# esc_control.net
KiCad netlist of a schematic drawn in EAGLE
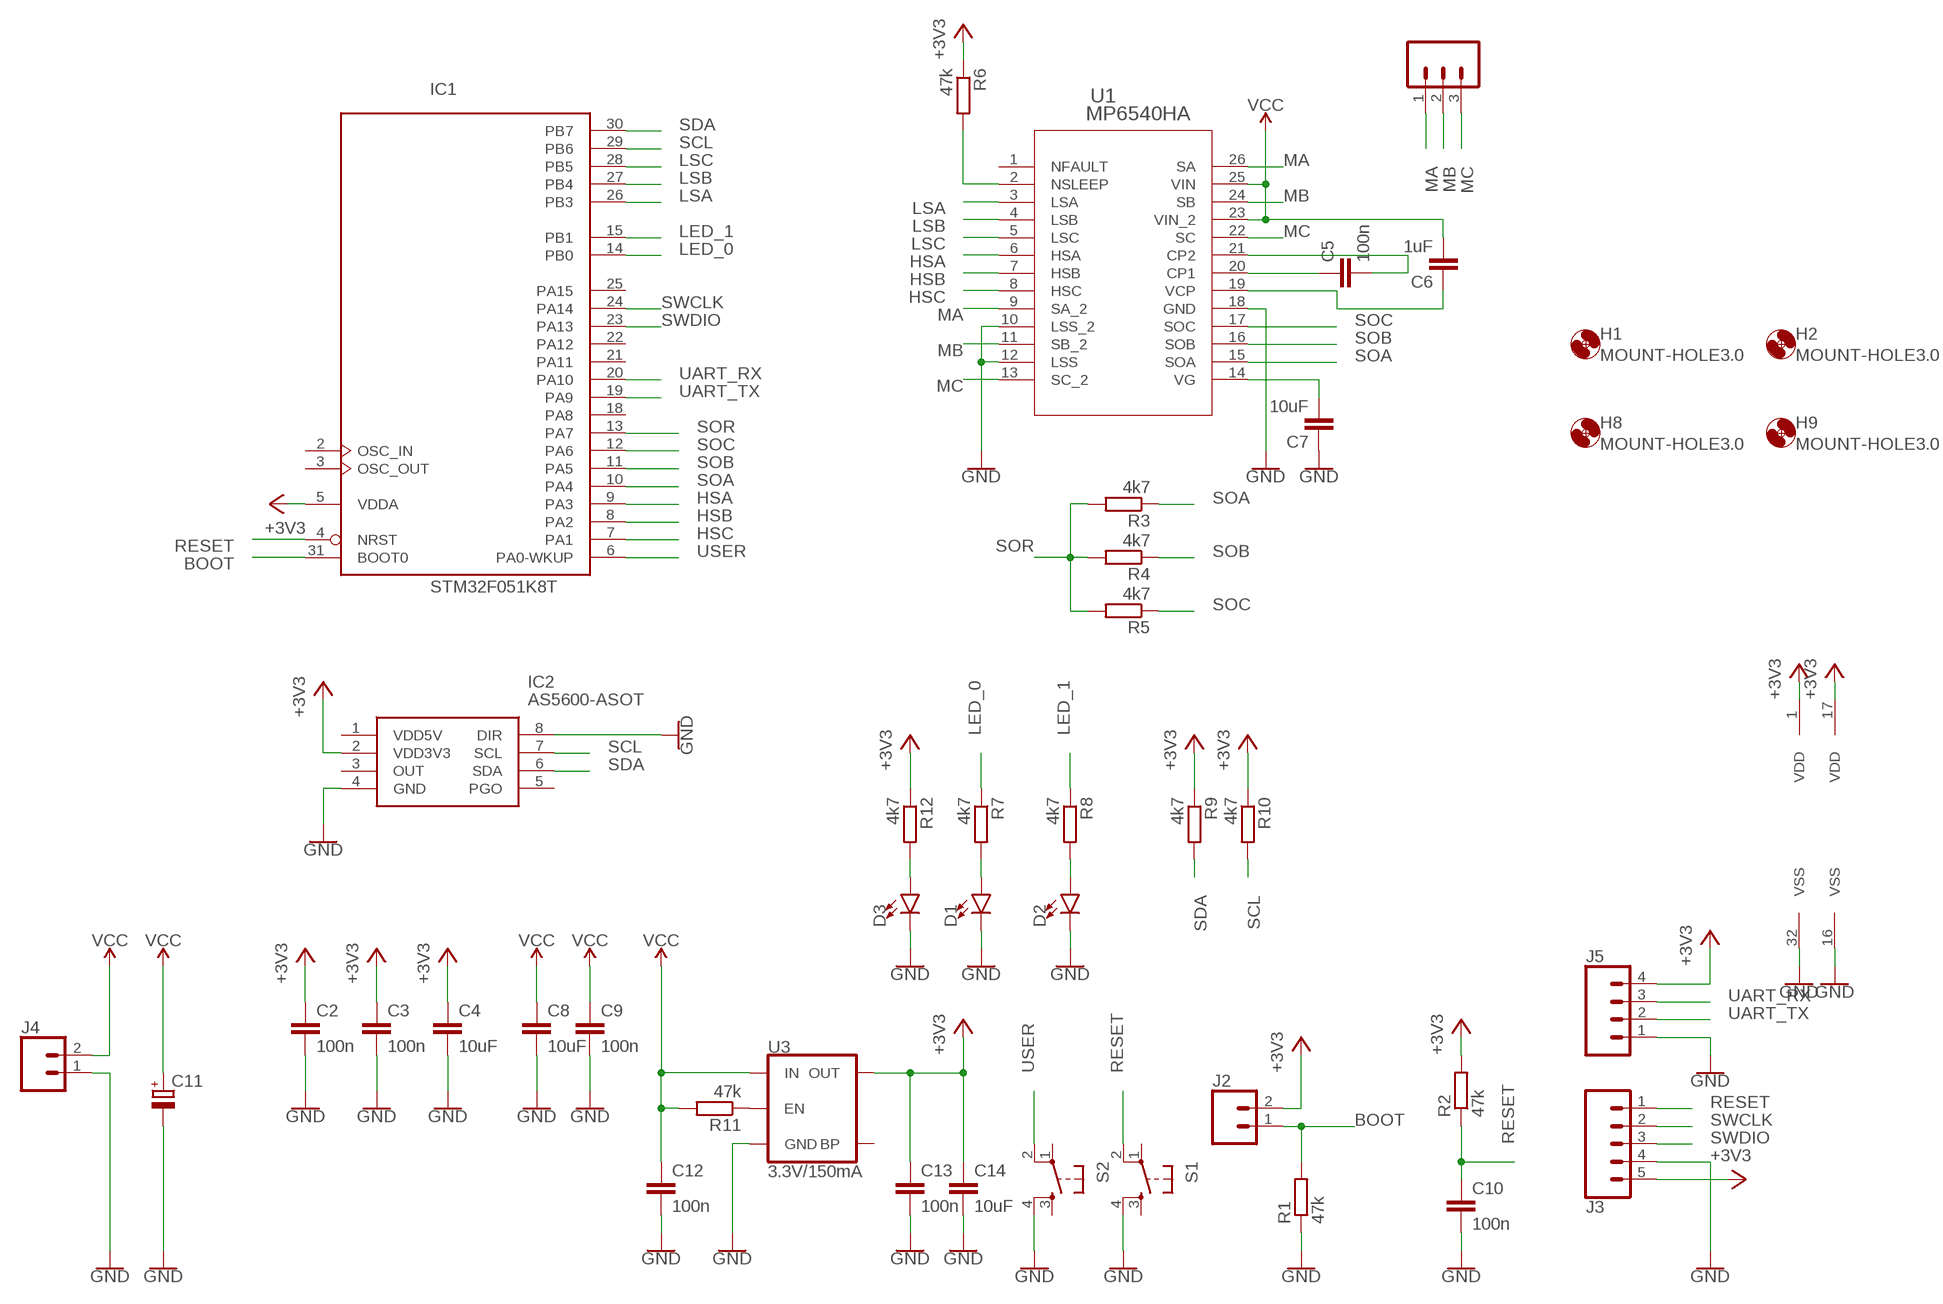
[diagram p0: schematic, sheet 1]

(export (version "E")
  (design (tool "Eeschema 10.0.6"))
  (components
    (comp (ref "C2")
      (value "100n")
      (footprint "eagle-import:C0805")
      (libsource (lib "eagle-import") (part "C-EUC0805"))
    )
    (comp (ref "C3")
      (value "100n")
      (footprint "eagle-import:C0805")
      (libsource (lib "eagle-import") (part "C-EUC0805"))
    )
    (comp (ref "C4")
      (value "10uF")
      (footprint "eagle-import:C0805")
      (libsource (lib "eagle-import") (part "C-EUC0805"))
    )
    (comp (ref "C5")
      (value "100n")
      (footprint "eagle-import:C0805")
      (libsource (lib "eagle-import") (part "C-EUC0805"))
    )
    (comp (ref "C6")
      (value "1uF")
      (footprint "eagle-import:C0805")
      (libsource (lib "eagle-import") (part "C-EUC0805"))
    )
    (comp (ref "C7")
      (value "10uF")
      (footprint "eagle-import:C0805")
      (libsource (lib "eagle-import") (part "C-EUC0805"))
    )
    (comp (ref "C8")
      (value "10uF")
      (footprint "eagle-import:C0805")
      (libsource (lib "eagle-import") (part "C-EUC0805"))
    )
    (comp (ref "C9")
      (value "100n")
      (footprint "eagle-import:C0805")
      (libsource (lib "eagle-import") (part "C-EUC0805"))
    )
    (comp (ref "C10")
      (value "100n")
      (footprint "eagle-import:C0805")
      (libsource (lib "eagle-import") (part "C-EUC0805"))
    )
    (comp (ref "C11")
      (value "CPOL-EU153CLV-0605")
      (footprint "eagle-import:153CLV-0605")
      (libsource (lib "eagle-import") (part "CPOL-EU153CLV-0605"))
    )
    (comp (ref "C12")
      (value "100n")
      (footprint "eagle-import:C0805")
      (libsource (lib "eagle-import") (part "C-EUC0805"))
    )
    (comp (ref "C13")
      (value "100n")
      (footprint "eagle-import:C0805")
      (libsource (lib "eagle-import") (part "C-EUC0805"))
    )
    (comp (ref "C14")
      (value "10uF")
      (footprint "eagle-import:C0805")
      (libsource (lib "eagle-import") (part "C-EUC0805"))
    )
    (comp (ref "D1")
      (value "LED1206")
      (footprint "eagle-import:LED-1206")
      (libsource (lib "eagle-import") (part "LED1206"))
    )
    (comp (ref "D2")
      (value "LED1206")
      (footprint "eagle-import:LED-1206")
      (libsource (lib "eagle-import") (part "LED1206"))
    )
    (comp (ref "D3")
      (value "LED1206")
      (footprint "eagle-import:LED-1206")
      (libsource (lib "eagle-import") (part "LED1206"))
    )
    (comp (ref "H1")
      (value "MOUNT-HOLE3.0")
      (footprint "eagle-import:3,0")
      (libsource (lib "eagle-import") (part "MOUNT-HOLE3.0"))
    )
    (comp (ref "H2")
      (value "MOUNT-HOLE3.0")
      (footprint "eagle-import:3,0")
      (libsource (lib "eagle-import") (part "MOUNT-HOLE3.0"))
    )
    (comp (ref "H8")
      (value "MOUNT-HOLE3.0")
      (footprint "eagle-import:3,0")
      (libsource (lib "eagle-import") (part "MOUNT-HOLE3.0"))
    )
    (comp (ref "H9")
      (value "MOUNT-HOLE3.0")
      (footprint "eagle-import:3,0")
      (libsource (lib "eagle-import") (part "MOUNT-HOLE3.0"))
    )
    (comp (ref "IC1")
      (value "STM32F051K8T")
      (footprint "eagle-import:LQFP32")
      (libsource (lib "eagle-import") (part "STM32F051KT8"))
    )
    (comp (ref "IC2")
      (value "AS5600-ASOT")
      (footprint "eagle-import:SOIC127P600X175-8N")
      (fields (field (name "MOUSER_PART_NUMBER") "985-AS5600-ASOT"))
      (libsource (lib "eagle-import") (part "AS5600-ASOT"))
    )
    (comp (ref "J1")
      (value "455-1750-1-ND")
      (footprint "eagle-import:1X03")
      (libsource (lib "eagle-import") (part "CONN_03"))
    )
    (comp (ref "J2")
      (value "CONN_02PTH3")
      (footprint "eagle-import:1X02_LONGPADS")
      (libsource (lib "eagle-import") (part "CONN_02PTH3"))
    )
    (comp (ref "J3")
      (value "CONN_05PTH_LONGPADS")
      (footprint "eagle-import:1X05_LONGPADS")
      (libsource (lib "eagle-import") (part "CONN_05PTH_LONGPADS"))
    )
    (comp (ref "J4")
      (value "CONN_02PTH3")
      (footprint "eagle-import:1X02_LONGPADS")
      (libsource (lib "eagle-import") (part "CONN_02PTH3"))
    )
    (comp (ref "J5")
      (value "CONN_04LONGPADS")
      (footprint "eagle-import:1X04_LONGPADS")
      (libsource (lib "eagle-import") (part "CONN_04LONGPADS"))
    )
    (comp (ref "R1")
      (value "47k")
      (footprint "eagle-import:M0805")
      (libsource (lib "eagle-import") (part "R-EU_M0805"))
    )
    (comp (ref "R2")
      (value "47k")
      (footprint "eagle-import:M0805")
      (libsource (lib "eagle-import") (part "R-EU_M0805"))
    )
    (comp (ref "R3")
      (value "4k7")
      (footprint "eagle-import:M0805")
      (libsource (lib "eagle-import") (part "R-EU_M0805"))
    )
    (comp (ref "R4")
      (value "4k7")
      (footprint "eagle-import:M0805")
      (libsource (lib "eagle-import") (part "R-EU_M0805"))
    )
    (comp (ref "R5")
      (value "4k7")
      (footprint "eagle-import:M0805")
      (libsource (lib "eagle-import") (part "R-EU_M0805"))
    )
    (comp (ref "R6")
      (value "47k")
      (footprint "eagle-import:M0805")
      (libsource (lib "eagle-import") (part "R-EU_M0805"))
    )
    (comp (ref "R7")
      (value "4k7")
      (footprint "eagle-import:M0805")
      (libsource (lib "eagle-import") (part "R-EU_M0805"))
    )
    (comp (ref "R8")
      (value "4k7")
      (footprint "eagle-import:M0805")
      (libsource (lib "eagle-import") (part "R-EU_M0805"))
    )
    (comp (ref "R9")
      (value "4k7")
      (footprint "eagle-import:M0805")
      (libsource (lib "eagle-import") (part "R-EU_M0805"))
    )
    (comp (ref "R10")
      (value "4k7")
      (footprint "eagle-import:M0805")
      (libsource (lib "eagle-import") (part "R-EU_M0805"))
    )
    (comp (ref "R11")
      (value "47k")
      (footprint "eagle-import:M0805")
      (libsource (lib "eagle-import") (part "R-EU_M0805"))
    )
    (comp (ref "R12")
      (value "4k7")
      (footprint "eagle-import:M0805")
      (libsource (lib "eagle-import") (part "R-EU_M0805"))
    )
    (comp (ref "S1")
      (value "TAC_SWITCHSMD")
      (footprint "eagle-import:TACTILE-SWITCH-SMD")
      (libsource (lib "eagle-import") (part "TAC_SWITCHSMD"))
    )
    (comp (ref "S2")
      (value "TAC_SWITCHSMD")
      (footprint "eagle-import:TACTILE-SWITCH-SMD")
      (libsource (lib "eagle-import") (part "TAC_SWITCHSMD"))
    )
    (comp (ref "U1")
      (value "MP6540HA")
      (footprint "eagle-import:QFN-5X5_MP6540HA_MNP")
      (fields (field (name "COPYRIGHT") "Copyright (C) 2018 Accelerated Designs. All rights reserved"))
      (libsource (lib "eagle-import") (part "MP6540HA"))
    )
    (comp (ref "U3")
      (value "3.3V/150mA")
      (footprint "eagle-import:SOT23-5")
      (libsource (lib "eagle-import") (part "V_REG_MIC52053.3V"))
    )
  )
  (nets
    (net (code "1") (name "+3V3") (class "Default")
      (node (ref "C13") (pin "1") (pinfunction "1_1") (pintype "passive"))
      (node (ref "C14") (pin "1") (pinfunction "1_1") (pintype "passive"))
      (node (ref "C2") (pin "1") (pinfunction "1_1") (pintype "passive"))
      (node (ref "C3") (pin "1") (pinfunction "1_1") (pintype "passive"))
      (node (ref "C4") (pin "1") (pinfunction "1_1") (pintype "passive"))
      (node (ref "IC1") (pin "1") (pinfunction "VDD_1") (pintype "power_in"))
      (node (ref "IC1") (pin "17") (pinfunction "VDD_17") (pintype "power_in"))
      (node (ref "IC1") (pin "5") (pinfunction "VDDA_5") (pintype "power_in"))
      (node (ref "IC2") (pin "2") (pinfunction "VDD3V3_2") (pintype "bidirectional"))
      (node (ref "J2") (pin "2") (pinfunction "2_2") (pintype "passive"))
      (node (ref "J3") (pin "5") (pinfunction "5_5") (pintype "passive"))
      (node (ref "J5") (pin "4") (pinfunction "4_4") (pintype "passive"))
      (node (ref "R10") (pin "1") (pinfunction "1_1") (pintype "passive"))
      (node (ref "R12") (pin "1") (pinfunction "1_1") (pintype "passive"))
      (node (ref "R2") (pin "2") (pinfunction "2_2") (pintype "passive"))
      (node (ref "R6") (pin "1") (pinfunction "1_1") (pintype "passive"))
      (node (ref "R9") (pin "1") (pinfunction "1_1") (pintype "passive"))
      (node (ref "U3") (pin "5") (pinfunction "OUT_5") (pintype "passive"))
    )
    (net (code "2") (name "/BOOT") (class "Default")
      (node (ref "IC1") (pin "31") (pinfunction "BOOT0_31") (pintype "input"))
      (node (ref "J2") (pin "1") (pinfunction "1_1") (pintype "passive"))
      (node (ref "R1") (pin "2") (pinfunction "2_2") (pintype "passive"))
    )
    (net (code "3") (name "/HSA") (class "Default")
      (node (ref "IC1") (pin "9") (pinfunction "PA3_9") (pintype "bidirectional"))
      (node (ref "U1") (pin "6") (pinfunction "HSA_6") (pintype "passive"))
    )
    (net (code "4") (name "/HSB") (class "Default")
      (node (ref "IC1") (pin "8") (pinfunction "PA2_8") (pintype "bidirectional"))
      (node (ref "U1") (pin "7") (pinfunction "HSB_7") (pintype "passive"))
    )
    (net (code "5") (name "/HSC") (class "Default")
      (node (ref "IC1") (pin "7") (pinfunction "PA1_7") (pintype "bidirectional"))
      (node (ref "U1") (pin "8") (pinfunction "HSC_8") (pintype "passive"))
    )
    (net (code "6") (name "/LED_0") (class "Default")
      (node (ref "IC1") (pin "14") (pinfunction "PB0_14") (pintype "bidirectional"))
      (node (ref "R7") (pin "1") (pinfunction "1_1") (pintype "passive"))
    )
    (net (code "7") (name "/LED_1") (class "Default")
      (node (ref "IC1") (pin "15") (pinfunction "PB1_15") (pintype "bidirectional"))
      (node (ref "R8") (pin "1") (pinfunction "1_1") (pintype "passive"))
    )
    (net (code "8") (name "/LSA") (class "Default")
      (node (ref "IC1") (pin "26") (pinfunction "PB3_26") (pintype "bidirectional"))
      (node (ref "U1") (pin "3") (pinfunction "LSA_3") (pintype "passive"))
    )
    (net (code "9") (name "/LSB") (class "Default")
      (node (ref "IC1") (pin "27") (pinfunction "PB4_27") (pintype "bidirectional"))
      (node (ref "U1") (pin "4") (pinfunction "LSB_4") (pintype "passive"))
    )
    (net (code "10") (name "/LSC") (class "Default")
      (node (ref "IC1") (pin "28") (pinfunction "PB5_28") (pintype "bidirectional"))
      (node (ref "U1") (pin "5") (pinfunction "LSC_5") (pintype "passive"))
    )
    (net (code "11") (name "/MA") (class "Default")
      (node (ref "J1") (pin "1") (pinfunction "1_1") (pintype "passive"))
      (node (ref "U1") (pin "26") (pinfunction "SA_26") (pintype "output"))
      (node (ref "U1") (pin "9") (pinfunction "SA_2_9") (pintype "output"))
    )
    (net (code "12") (name "/MB") (class "Default")
      (node (ref "J1") (pin "2") (pinfunction "2_2") (pintype "passive"))
      (node (ref "U1") (pin "11") (pinfunction "SB_2_11") (pintype "output"))
      (node (ref "U1") (pin "24") (pinfunction "SB_24") (pintype "output"))
    )
    (net (code "13") (name "/MC") (class "Default")
      (node (ref "J1") (pin "3") (pinfunction "3_3") (pintype "passive"))
      (node (ref "U1") (pin "13") (pinfunction "SC_2_13") (pintype "output"))
      (node (ref "U1") (pin "22") (pinfunction "SC_22") (pintype "output"))
    )
    (net (code "14") (name "/RESET") (class "Default")
      (node (ref "C10") (pin "1") (pinfunction "1_1") (pintype "passive"))
      (node (ref "IC1") (pin "4") (pinfunction "NRST_4") (pintype "bidirectional"))
      (node (ref "J3") (pin "1") (pinfunction "1_1") (pintype "passive"))
      (node (ref "R2") (pin "1") (pinfunction "1_1") (pintype "passive"))
      (node (ref "S1") (pin "2") (pinfunction "2_2") (pintype "passive"))
    )
    (net (code "15") (name "/SCL") (class "Default")
      (node (ref "IC1") (pin "29") (pinfunction "PB6_29") (pintype "bidirectional"))
      (node (ref "IC2") (pin "7") (pinfunction "SCL_7") (pintype "bidirectional"))
      (node (ref "R10") (pin "2") (pinfunction "2_2") (pintype "passive"))
    )
    (net (code "16") (name "/SDA") (class "Default")
      (node (ref "IC1") (pin "30") (pinfunction "PB7_30") (pintype "bidirectional"))
      (node (ref "IC2") (pin "6") (pinfunction "SDA_6") (pintype "bidirectional"))
      (node (ref "R9") (pin "2") (pinfunction "2_2") (pintype "passive"))
    )
    (net (code "17") (name "/SOA") (class "Default")
      (node (ref "IC1") (pin "10") (pinfunction "PA4_10") (pintype "bidirectional"))
      (node (ref "R3") (pin "1") (pinfunction "1_1") (pintype "passive"))
      (node (ref "U1") (pin "15") (pinfunction "SOA_15") (pintype "output"))
    )
    (net (code "18") (name "/SOB") (class "Default")
      (node (ref "IC1") (pin "11") (pinfunction "PA5_11") (pintype "bidirectional"))
      (node (ref "R4") (pin "1") (pinfunction "1_1") (pintype "passive"))
      (node (ref "U1") (pin "16") (pinfunction "SOB_16") (pintype "output"))
    )
    (net (code "19") (name "/SOC") (class "Default")
      (node (ref "IC1") (pin "12") (pinfunction "PA6_12") (pintype "bidirectional"))
      (node (ref "R5") (pin "1") (pinfunction "1_1") (pintype "passive"))
      (node (ref "U1") (pin "17") (pinfunction "SOC_17") (pintype "output"))
    )
    (net (code "20") (name "/SOR") (class "Default")
      (node (ref "IC1") (pin "13") (pinfunction "PA7_13") (pintype "bidirectional"))
      (node (ref "R3") (pin "2") (pinfunction "2_2") (pintype "passive"))
      (node (ref "R4") (pin "2") (pinfunction "2_2") (pintype "passive"))
      (node (ref "R5") (pin "2") (pinfunction "2_2") (pintype "passive"))
    )
    (net (code "21") (name "/SWCLK") (class "Default")
      (node (ref "IC1") (pin "24") (pinfunction "PA14_24") (pintype "bidirectional"))
      (node (ref "J3") (pin "2") (pinfunction "2_2") (pintype "passive"))
    )
    (net (code "22") (name "/SWDIO") (class "Default")
      (node (ref "IC1") (pin "23") (pinfunction "PA13_23") (pintype "bidirectional"))
      (node (ref "J3") (pin "3") (pinfunction "3_3") (pintype "passive"))
    )
    (net (code "23") (name "/UART_RX") (class "Default")
      (node (ref "IC1") (pin "20") (pinfunction "PA10_20") (pintype "bidirectional"))
      (node (ref "J5") (pin "3") (pinfunction "3_3") (pintype "passive"))
    )
    (net (code "24") (name "/UART_TX") (class "Default")
      (node (ref "IC1") (pin "19") (pinfunction "PA9_19") (pintype "bidirectional"))
      (node (ref "J5") (pin "2") (pinfunction "2_2") (pintype "passive"))
    )
    (net (code "25") (name "/USER") (class "Default")
      (node (ref "IC1") (pin "6") (pinfunction "PA0-WKUP_6") (pintype "bidirectional"))
      (node (ref "S2") (pin "2") (pinfunction "2_2") (pintype "passive"))
    )
    (net (code "26") (name "GND") (class "Default")
      (node (ref "C10") (pin "2") (pinfunction "2_2") (pintype "passive"))
      (node (ref "C11") (pin "-") (pinfunction "-_-") (pintype "passive"))
      (node (ref "C12") (pin "2") (pinfunction "2_2") (pintype "passive"))
      (node (ref "C13") (pin "2") (pinfunction "2_2") (pintype "passive"))
      (node (ref "C14") (pin "2") (pinfunction "2_2") (pintype "passive"))
      (node (ref "C2") (pin "2") (pinfunction "2_2") (pintype "passive"))
      (node (ref "C3") (pin "2") (pinfunction "2_2") (pintype "passive"))
      (node (ref "C4") (pin "2") (pinfunction "2_2") (pintype "passive"))
      (node (ref "C7") (pin "1") (pinfunction "1_1") (pintype "passive"))
      (node (ref "C8") (pin "2") (pinfunction "2_2") (pintype "passive"))
      (node (ref "C9") (pin "2") (pinfunction "2_2") (pintype "passive"))
      (node (ref "D1") (pin "C") (pinfunction "C_C") (pintype "passive"))
      (node (ref "D2") (pin "C") (pinfunction "C_C") (pintype "passive"))
      (node (ref "D3") (pin "C") (pinfunction "C_C") (pintype "passive"))
      (node (ref "IC1") (pin "16") (pinfunction "VSS_16") (pintype "power_in"))
      (node (ref "IC1") (pin "32") (pinfunction "VSS_32") (pintype "power_in"))
      (node (ref "IC2") (pin "4") (pinfunction "GND_4") (pintype "bidirectional"))
      (node (ref "IC2") (pin "8") (pinfunction "DIR_8") (pintype "bidirectional"))
      (node (ref "J3") (pin "4") (pinfunction "4_4") (pintype "passive"))
      (node (ref "J4") (pin "1") (pinfunction "1_1") (pintype "passive"))
      (node (ref "J5") (pin "1") (pinfunction "1_1") (pintype "passive"))
      (node (ref "R1") (pin "1") (pinfunction "1_1") (pintype "passive"))
      (node (ref "S1") (pin "4") (pinfunction "4_4") (pintype "passive"))
      (node (ref "S2") (pin "4") (pinfunction "4_4") (pintype "passive"))
      (node (ref "U1") (pin "10") (pinfunction "LSS_2_10") (pintype "passive"))
      (node (ref "U1") (pin "12") (pinfunction "LSS_12") (pintype "passive"))
      (node (ref "U1") (pin "18") (pinfunction "GND_18") (pintype "passive"))
      (node (ref "U3") (pin "2") (pinfunction "GND_2") (pintype "input"))
    )
    (net (code "27") (name "Net-(D1-PadA)") (class "Default")
      (node (ref "D1") (pin "A") (pinfunction "A_A") (pintype "passive"))
      (node (ref "R7") (pin "2") (pinfunction "2_2") (pintype "passive"))
    )
    (net (code "28") (name "Net-(D2-PadA)") (class "Default")
      (node (ref "D2") (pin "A") (pinfunction "A_A") (pintype "passive"))
      (node (ref "R8") (pin "2") (pinfunction "2_2") (pintype "passive"))
    )
    (net (code "29") (name "Net-(D3-PadA)") (class "Default")
      (node (ref "D3") (pin "A") (pinfunction "A_A") (pintype "passive"))
      (node (ref "R12") (pin "2") (pinfunction "2_2") (pintype "passive"))
    )
    (net (code "30") (name "Net-(U1-CP1)") (class "Default")
      (node (ref "C5") (pin "1") (pinfunction "1_1") (pintype "passive"))
      (node (ref "U1") (pin "20") (pinfunction "CP1_20") (pintype "passive"))
    )
    (net (code "31") (name "Net-(U1-CP2)") (class "Default")
      (node (ref "C5") (pin "2") (pinfunction "2_2") (pintype "passive"))
      (node (ref "U1") (pin "21") (pinfunction "CP2_21") (pintype "passive"))
    )
    (net (code "32") (name "Net-(U1-NSLEEP)") (class "Default")
      (node (ref "R6") (pin "2") (pinfunction "2_2") (pintype "passive"))
      (node (ref "U1") (pin "2") (pinfunction "NSLEEP_2") (pintype "input"))
    )
    (net (code "33") (name "Net-(U1-VCP)") (class "Default")
      (node (ref "C6") (pin "1") (pinfunction "1_1") (pintype "passive"))
      (node (ref "U1") (pin "19") (pinfunction "VCP_19") (pintype "output"))
    )
    (net (code "34") (name "Net-(U1-VG)") (class "Default")
      (node (ref "C7") (pin "2") (pinfunction "2_2") (pintype "passive"))
      (node (ref "U1") (pin "14") (pinfunction "VG_14") (pintype "power_in"))
    )
    (net (code "35") (name "Net-(U3-EN)") (class "Default")
      (node (ref "R11") (pin "1") (pinfunction "1_1") (pintype "passive"))
      (node (ref "U3") (pin "3") (pinfunction "EN_3") (pintype "input"))
    )
    (net (code "36") (name "VCC") (class "Default")
      (node (ref "C11") (pin "+") (pinfunction "+_+") (pintype "passive"))
      (node (ref "C12") (pin "1") (pinfunction "1_1") (pintype "passive"))
      (node (ref "C6") (pin "2") (pinfunction "2_2") (pintype "passive"))
      (node (ref "C8") (pin "1") (pinfunction "1_1") (pintype "passive"))
      (node (ref "C9") (pin "1") (pinfunction "1_1") (pintype "passive"))
      (node (ref "J4") (pin "2") (pinfunction "2_2") (pintype "passive"))
      (node (ref "R11") (pin "2") (pinfunction "2_2") (pintype "passive"))
      (node (ref "U1") (pin "23") (pinfunction "VIN_2_23") (pintype "power_in"))
      (node (ref "U1") (pin "25") (pinfunction "VIN_25") (pintype "power_in"))
      (node (ref "U3") (pin "1") (pinfunction "IN_1") (pintype "input"))
    )
    (net (code "37") (name "unconnected-(IC1A-OSC_IN-Pad2)") (class "Default")
      (node (ref "IC1") (pin "2") (pinfunction "OSC_IN_2") (pintype "bidirectional"))
    )
    (net (code "38") (name "unconnected-(IC1A-OSC_OUT-Pad3)") (class "Default")
      (node (ref "IC1") (pin "3") (pinfunction "OSC_OUT_3") (pintype "bidirectional"))
    )
    (net (code "39") (name "unconnected-(IC1A-PA8-Pad18)") (class "Default")
      (node (ref "IC1") (pin "18") (pinfunction "PA8_18") (pintype "bidirectional"))
    )
    (net (code "40") (name "unconnected-(IC1A-PA11-Pad21)") (class "Default")
      (node (ref "IC1") (pin "21") (pinfunction "PA11_21") (pintype "bidirectional"))
    )
    (net (code "41") (name "unconnected-(IC1A-PA12-Pad22)") (class "Default")
      (node (ref "IC1") (pin "22") (pinfunction "PA12_22") (pintype "bidirectional"))
    )
    (net (code "42") (name "unconnected-(IC1A-PA15-Pad25)") (class "Default")
      (node (ref "IC1") (pin "25") (pinfunction "PA15_25") (pintype "bidirectional"))
    )
    (net (code "43") (name "unconnected-(IC2-OUT-Pad3)") (class "Default")
      (node (ref "IC2") (pin "3") (pinfunction "OUT_3") (pintype "bidirectional"))
    )
    (net (code "44") (name "unconnected-(IC2-PGO-Pad5)") (class "Default")
      (node (ref "IC2") (pin "5") (pinfunction "PGO_5") (pintype "bidirectional"))
    )
    (net (code "45") (name "unconnected-(IC2-VDD5V-Pad1)") (class "Default")
      (node (ref "IC2") (pin "1") (pinfunction "VDD5V_1") (pintype "bidirectional"))
    )
    (net (code "46") (name "unconnected-(S1-Pad1)") (class "Default")
      (node (ref "S1") (pin "1") (pinfunction "1_1") (pintype "passive"))
    )
    (net (code "47") (name "unconnected-(S1-Pad3)") (class "Default")
      (node (ref "S1") (pin "3") (pinfunction "3_3") (pintype "passive"))
    )
    (net (code "48") (name "unconnected-(S2-Pad1)") (class "Default")
      (node (ref "S2") (pin "1") (pinfunction "1_1") (pintype "passive"))
    )
    (net (code "49") (name "unconnected-(S2-Pad3)") (class "Default")
      (node (ref "S2") (pin "3") (pinfunction "3_3") (pintype "passive"))
    )
    (net (code "50") (name "unconnected-(U1-NFAULT-Pad1)") (class "Default")
      (node (ref "U1") (pin "1") (pinfunction "NFAULT_1") (pintype "output"))
    )
    (net (code "51") (name "unconnected-(U3-BP-Pad4)") (class "Default")
      (node (ref "U3") (pin "4") (pinfunction "BP_4") (pintype "input"))
    )
  )
)
